# ham_filter.net
KiCad netlist of a schematic drawn in EAGLE
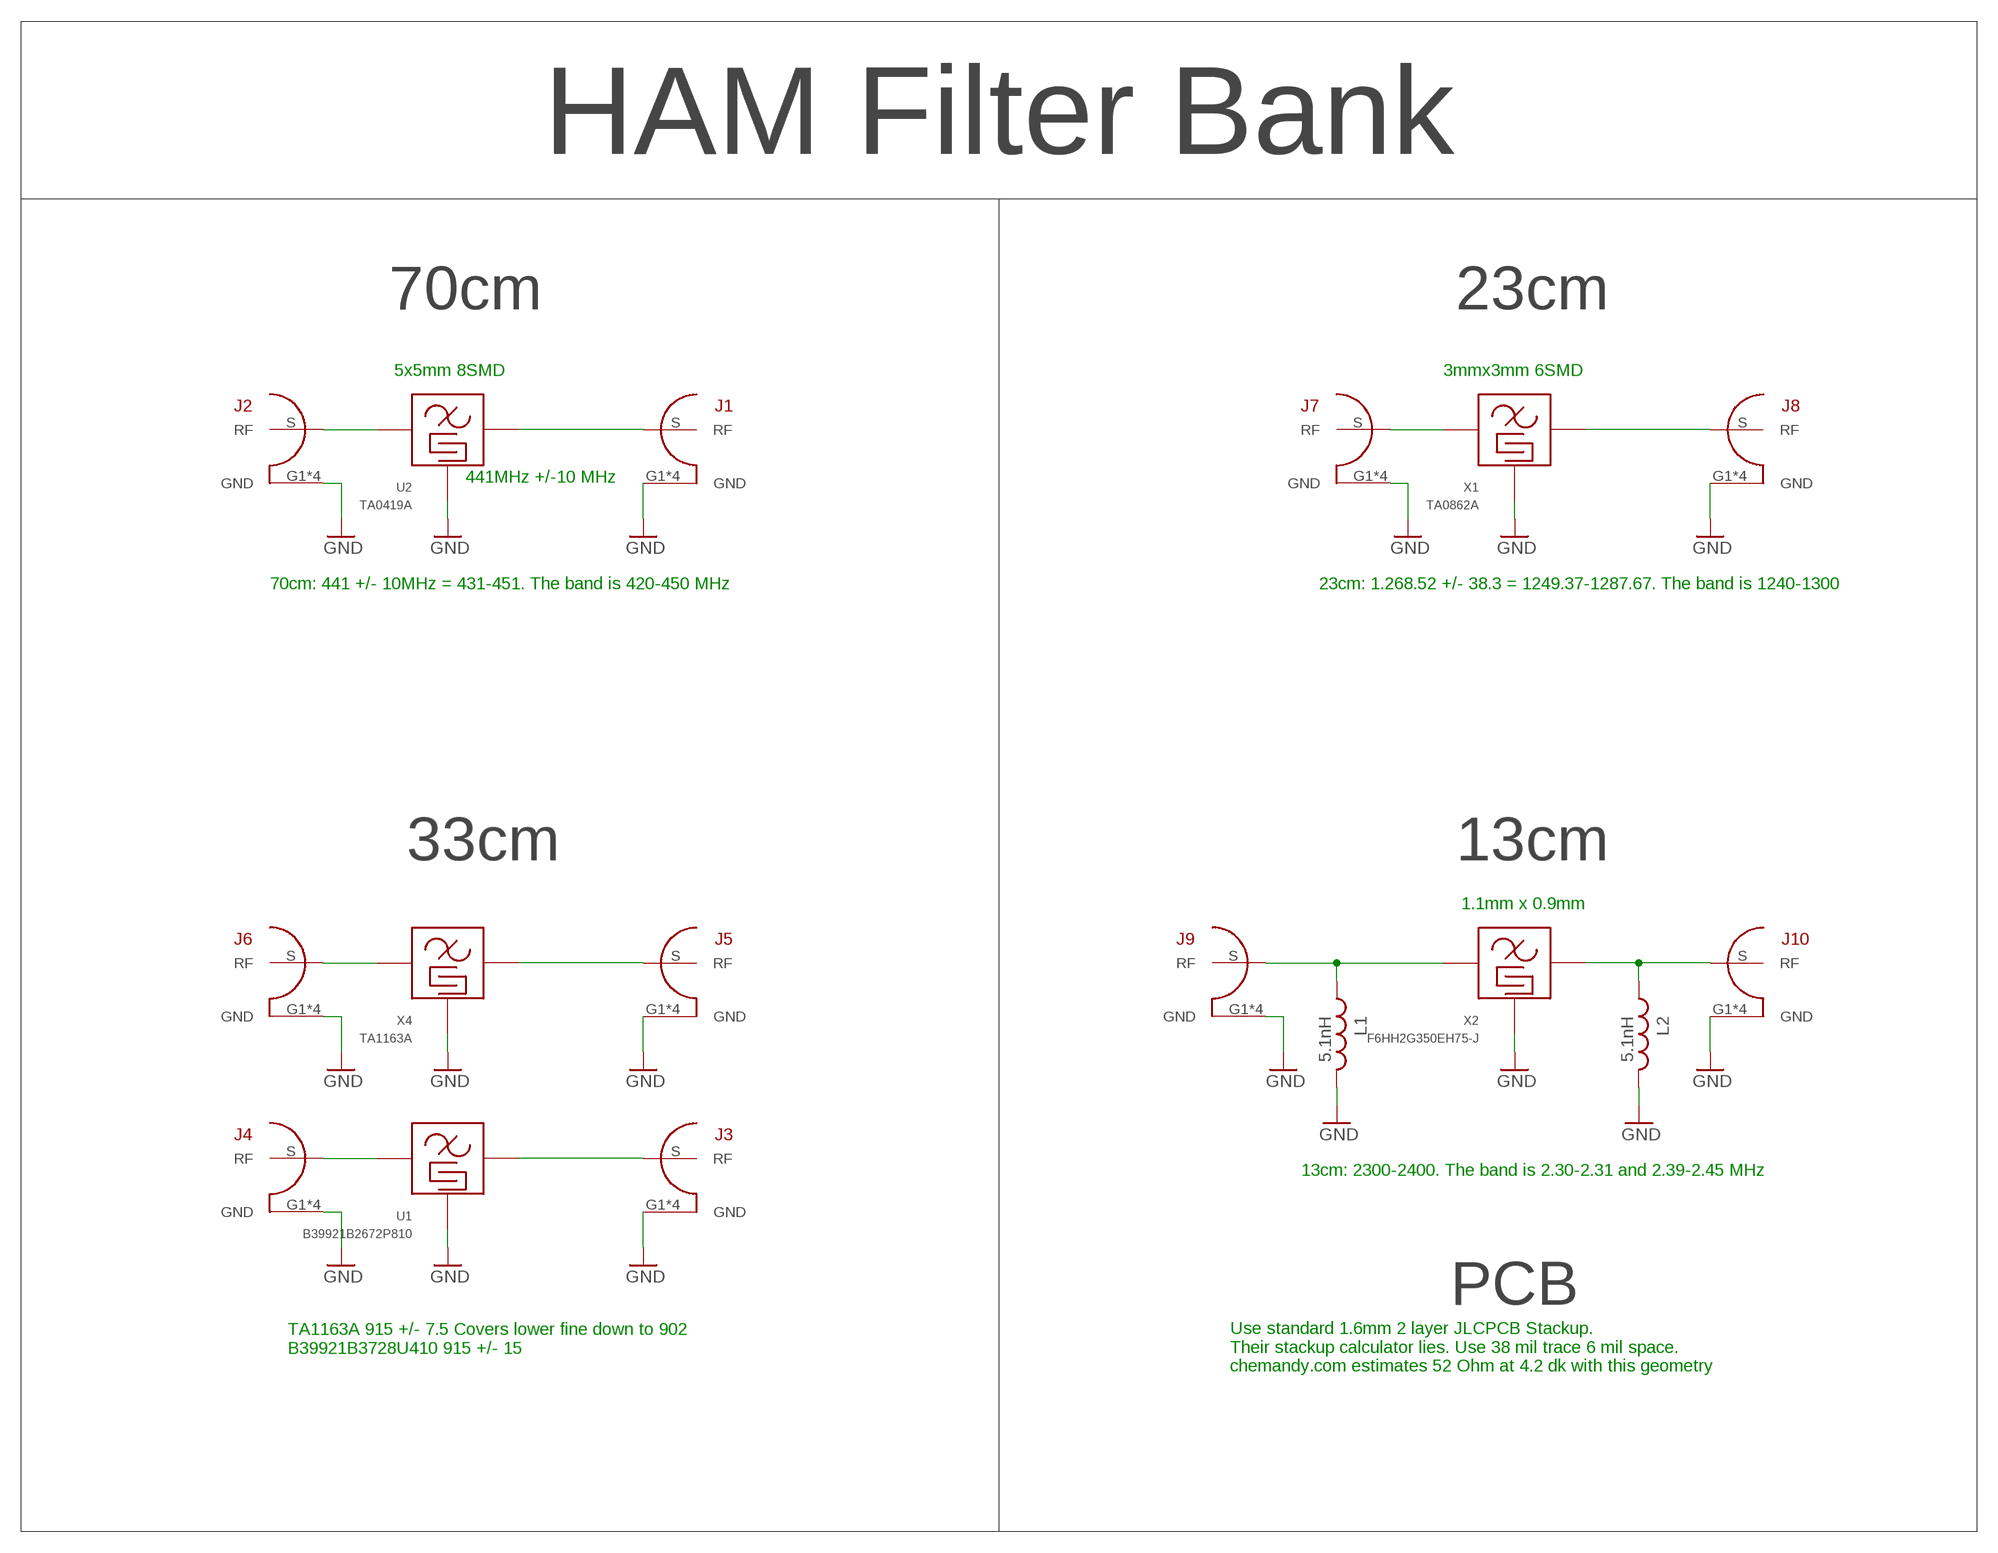
[diagram p0: schematic, sheet 1]

(export (version "E")
  (design (tool "Eeschema 10.0.6"))
  (components
    (comp (ref "J1")
      (value "0733910070")
      (footprint "eagle-import:CONREVSMA008-G")
      (fields (field (name "PARTNO") "WM5544-ND"))
      (libsource (lib "eagle-import") (part "0733910070"))
    )
    (comp (ref "J2")
      (value "0733910070")
      (footprint "eagle-import:CONREVSMA008-G")
      (fields (field (name "PARTNO") "WM5544-ND"))
      (libsource (lib "eagle-import") (part "0733910070"))
    )
    (comp (ref "J3")
      (value "0733910070")
      (footprint "eagle-import:CONREVSMA008-G")
      (fields (field (name "PARTNO") "WM5544-ND"))
      (libsource (lib "eagle-import") (part "0733910070"))
    )
    (comp (ref "J4")
      (value "0733910070")
      (footprint "eagle-import:CONREVSMA008-G")
      (fields (field (name "PARTNO") "WM5544-ND"))
      (libsource (lib "eagle-import") (part "0733910070"))
    )
    (comp (ref "J5")
      (value "0733910070")
      (footprint "eagle-import:CONREVSMA008-G")
      (fields (field (name "PARTNO") "WM5544-ND"))
      (libsource (lib "eagle-import") (part "0733910070"))
    )
    (comp (ref "J6")
      (value "0733910070")
      (footprint "eagle-import:CONREVSMA008-G")
      (fields (field (name "PARTNO") "WM5544-ND"))
      (libsource (lib "eagle-import") (part "0733910070"))
    )
    (comp (ref "J7")
      (value "0733910070")
      (footprint "eagle-import:CONREVSMA008-G")
      (fields (field (name "PARTNO") "WM5544-ND"))
      (libsource (lib "eagle-import") (part "0733910070"))
    )
    (comp (ref "J8")
      (value "0733910070")
      (footprint "eagle-import:CONREVSMA008-G")
      (fields (field (name "PARTNO") "WM5544-ND"))
      (libsource (lib "eagle-import") (part "0733910070"))
    )
    (comp (ref "J9")
      (value "0733910070")
      (footprint "eagle-import:CONREVSMA008-G")
      (fields (field (name "PARTNO") "WM5544-ND"))
      (libsource (lib "eagle-import") (part "0733910070"))
    )
    (comp (ref "J10")
      (value "0733910070")
      (footprint "eagle-import:CONREVSMA008-G")
      (fields (field (name "PARTNO") "WM5544-ND"))
      (libsource (lib "eagle-import") (part "0733910070"))
    )
    (comp (ref "L1")
      (value "5.1nH")
      (footprint "eagle-import:0402_INDUCTOR")
      (libsource (lib "eagle-import") (part "0402_INDUCTOR"))
    )
    (comp (ref "L2")
      (value "5.1nH")
      (footprint "eagle-import:0402_INDUCTOR")
      (libsource (lib "eagle-import") (part "0402_INDUCTOR"))
    )
    (comp (ref "U1")
      (value "B39921B2672P810")
      (footprint "eagle-import:B2672")
      (fields (field (name "PARTNO") "1752-B39921B2672P810CT-ND"))
      (libsource (lib "eagle-import") (part "B39921B2672P810"))
    )
    (comp (ref "U2")
      (value "TA0419A")
      (footprint "eagle-import:TAO419")
      (fields (field (name "PARTNO") "4606-TA0419ACT-ND"))
      (libsource (lib "eagle-import") (part "TA0419A"))
    )
    (comp (ref "X1")
      (value "TA0862A")
      (footprint "eagle-import:TA0862A")
      (fields (field (name "PARTNO") "4606-TA0862ACT-ND"))
      (libsource (lib "eagle-import") (part "TA0862A"))
    )
    (comp (ref "X2")
      (value "F6HH2G350EH75-J")
      (footprint "eagle-import:EH75")
      (fields (field (name "PARTNO") "587-F6HH2G350EH75-JCT-ND"))
      (libsource (lib "eagle-import") (part "F6HH2G350EH75-J"))
    )
    (comp (ref "X4")
      (value "TA1163A")
      (footprint "eagle-import:TA0862A")
      (fields (field (name "PARTNO") "4606-TA0862ACT-ND"))
      (libsource (lib "eagle-import") (part "TA0862A"))
    )
  )
  (nets
    (net (code "1") (name "GND") (class "Default")
      (node (ref "J1") (pin "G1") (pinfunction "GND_G1") (pintype "bidirectional"))
      (node (ref "J1") (pin "G2") (pinfunction "GND_G2") (pintype "bidirectional"))
      (node (ref "J1") (pin "G3") (pinfunction "GND_G3") (pintype "bidirectional"))
      (node (ref "J1") (pin "G4") (pinfunction "GND_G4") (pintype "bidirectional"))
      (node (ref "J10") (pin "G1") (pinfunction "GND_G1") (pintype "bidirectional"))
      (node (ref "J10") (pin "G2") (pinfunction "GND_G2") (pintype "bidirectional"))
      (node (ref "J10") (pin "G3") (pinfunction "GND_G3") (pintype "bidirectional"))
      (node (ref "J10") (pin "G4") (pinfunction "GND_G4") (pintype "bidirectional"))
      (node (ref "J2") (pin "G1") (pinfunction "GND_G1") (pintype "bidirectional"))
      (node (ref "J2") (pin "G2") (pinfunction "GND_G2") (pintype "bidirectional"))
      (node (ref "J2") (pin "G3") (pinfunction "GND_G3") (pintype "bidirectional"))
      (node (ref "J2") (pin "G4") (pinfunction "GND_G4") (pintype "bidirectional"))
      (node (ref "J3") (pin "G1") (pinfunction "GND_G1") (pintype "bidirectional"))
      (node (ref "J3") (pin "G2") (pinfunction "GND_G2") (pintype "bidirectional"))
      (node (ref "J3") (pin "G3") (pinfunction "GND_G3") (pintype "bidirectional"))
      (node (ref "J3") (pin "G4") (pinfunction "GND_G4") (pintype "bidirectional"))
      (node (ref "J4") (pin "G1") (pinfunction "GND_G1") (pintype "bidirectional"))
      (node (ref "J4") (pin "G2") (pinfunction "GND_G2") (pintype "bidirectional"))
      (node (ref "J4") (pin "G3") (pinfunction "GND_G3") (pintype "bidirectional"))
      (node (ref "J4") (pin "G4") (pinfunction "GND_G4") (pintype "bidirectional"))
      (node (ref "J5") (pin "G1") (pinfunction "GND_G1") (pintype "bidirectional"))
      (node (ref "J5") (pin "G2") (pinfunction "GND_G2") (pintype "bidirectional"))
      (node (ref "J5") (pin "G3") (pinfunction "GND_G3") (pintype "bidirectional"))
      (node (ref "J5") (pin "G4") (pinfunction "GND_G4") (pintype "bidirectional"))
      (node (ref "J6") (pin "G1") (pinfunction "GND_G1") (pintype "bidirectional"))
      (node (ref "J6") (pin "G2") (pinfunction "GND_G2") (pintype "bidirectional"))
      (node (ref "J6") (pin "G3") (pinfunction "GND_G3") (pintype "bidirectional"))
      (node (ref "J6") (pin "G4") (pinfunction "GND_G4") (pintype "bidirectional"))
      (node (ref "J7") (pin "G1") (pinfunction "GND_G1") (pintype "bidirectional"))
      (node (ref "J7") (pin "G2") (pinfunction "GND_G2") (pintype "bidirectional"))
      (node (ref "J7") (pin "G3") (pinfunction "GND_G3") (pintype "bidirectional"))
      (node (ref "J7") (pin "G4") (pinfunction "GND_G4") (pintype "bidirectional"))
      (node (ref "J8") (pin "G1") (pinfunction "GND_G1") (pintype "bidirectional"))
      (node (ref "J8") (pin "G2") (pinfunction "GND_G2") (pintype "bidirectional"))
      (node (ref "J8") (pin "G3") (pinfunction "GND_G3") (pintype "bidirectional"))
      (node (ref "J8") (pin "G4") (pinfunction "GND_G4") (pintype "bidirectional"))
      (node (ref "J9") (pin "G1") (pinfunction "GND_G1") (pintype "bidirectional"))
      (node (ref "J9") (pin "G2") (pinfunction "GND_G2") (pintype "bidirectional"))
      (node (ref "J9") (pin "G3") (pinfunction "GND_G3") (pintype "bidirectional"))
      (node (ref "J9") (pin "G4") (pinfunction "GND_G4") (pintype "bidirectional"))
      (node (ref "L1") (pin "P$2") (pinfunction "P$2_P$2") (pintype "bidirectional"))
      (node (ref "L2") (pin "P$2") (pinfunction "P$2_P$2") (pintype "bidirectional"))
      (node (ref "U1") (pin "2") (pinfunction "GND_2") (pintype "bidirectional"))
      (node (ref "U1") (pin "3") (pinfunction "GND_3") (pintype "bidirectional"))
      (node (ref "U1") (pin "5") (pinfunction "GND_5") (pintype "bidirectional"))
      (node (ref "U2") (pin "1") (pinfunction "GND_1") (pintype "bidirectional"))
      (node (ref "U2") (pin "3") (pinfunction "GND_3") (pintype "bidirectional"))
      (node (ref "U2") (pin "4") (pinfunction "GND_4") (pintype "bidirectional"))
      (node (ref "U2") (pin "5") (pinfunction "GND_5") (pintype "bidirectional"))
      (node (ref "U2") (pin "7") (pinfunction "GND_7") (pintype "bidirectional"))
      (node (ref "U2") (pin "8") (pinfunction "GND_8") (pintype "bidirectional"))
      (node (ref "X1") (pin "A") (pinfunction "GND_A") (pintype "bidirectional"))
      (node (ref "X1") (pin "C") (pinfunction "GND_C") (pintype "bidirectional"))
      (node (ref "X1") (pin "D") (pinfunction "GND_D") (pintype "bidirectional"))
      (node (ref "X1") (pin "F") (pinfunction "GND_F") (pintype "bidirectional"))
      (node (ref "X2") (pin "2") (pinfunction "GND_2") (pintype "bidirectional"))
      (node (ref "X2") (pin "3") (pinfunction "GND_3") (pintype "bidirectional"))
      (node (ref "X2") (pin "5") (pinfunction "GND_5") (pintype "bidirectional"))
      (node (ref "X4") (pin "A") (pinfunction "GND_A") (pintype "bidirectional"))
      (node (ref "X4") (pin "C") (pinfunction "GND_C") (pintype "bidirectional"))
      (node (ref "X4") (pin "D") (pinfunction "GND_D") (pintype "bidirectional"))
      (node (ref "X4") (pin "F") (pinfunction "GND_F") (pintype "bidirectional"))
    )
    (net (code "2") (name "Net-(J1-RF)") (class "Default")
      (node (ref "J1") (pin "S") (pinfunction "RF_S") (pintype "bidirectional"))
      (node (ref "U2") (pin "6") (pinfunction "P$2_6") (pintype "bidirectional"))
    )
    (net (code "3") (name "Net-(J2-RF)") (class "Default")
      (node (ref "J2") (pin "S") (pinfunction "RF_S") (pintype "bidirectional"))
      (node (ref "U2") (pin "2") (pinfunction "P$1_2") (pintype "bidirectional"))
    )
    (net (code "4") (name "Net-(J3-RF)") (class "Default")
      (node (ref "J3") (pin "S") (pinfunction "RF_S") (pintype "bidirectional"))
      (node (ref "U1") (pin "4") (pinfunction "P$2_4") (pintype "bidirectional"))
    )
    (net (code "5") (name "Net-(J4-RF)") (class "Default")
      (node (ref "J4") (pin "S") (pinfunction "RF_S") (pintype "bidirectional"))
      (node (ref "U1") (pin "1") (pinfunction "P$1_1") (pintype "bidirectional"))
    )
    (net (code "6") (name "Net-(J5-RF)") (class "Default")
      (node (ref "J5") (pin "S") (pinfunction "RF_S") (pintype "bidirectional"))
      (node (ref "X4") (pin "E") (pinfunction "P$2_E") (pintype "bidirectional"))
    )
    (net (code "7") (name "Net-(J6-RF)") (class "Default")
      (node (ref "J6") (pin "S") (pinfunction "RF_S") (pintype "bidirectional"))
      (node (ref "X4") (pin "B") (pinfunction "P$1_B") (pintype "bidirectional"))
    )
    (net (code "8") (name "Net-(J7-RF)") (class "Default")
      (node (ref "J7") (pin "S") (pinfunction "RF_S") (pintype "bidirectional"))
      (node (ref "X1") (pin "B") (pinfunction "P$1_B") (pintype "bidirectional"))
    )
    (net (code "9") (name "Net-(J8-RF)") (class "Default")
      (node (ref "J8") (pin "S") (pinfunction "RF_S") (pintype "bidirectional"))
      (node (ref "X1") (pin "E") (pinfunction "P$2_E") (pintype "bidirectional"))
    )
    (net (code "10") (name "Net-(J9-RF)") (class "Default")
      (node (ref "J9") (pin "S") (pinfunction "RF_S") (pintype "bidirectional"))
      (node (ref "L1") (pin "P$1") (pinfunction "P$1_P$1") (pintype "bidirectional"))
      (node (ref "X2") (pin "1") (pinfunction "P$1_1") (pintype "bidirectional"))
    )
    (net (code "11") (name "Net-(J10-RF)") (class "Default")
      (node (ref "J10") (pin "S") (pinfunction "RF_S") (pintype "bidirectional"))
      (node (ref "L2") (pin "P$1") (pinfunction "P$1_P$1") (pintype "bidirectional"))
      (node (ref "X2") (pin "4") (pinfunction "P$2_4") (pintype "bidirectional"))
    )
  )
)
